# ALtiumSTM32_schematic.net
KiCad netlist of a schematic drawn in Altium Designer
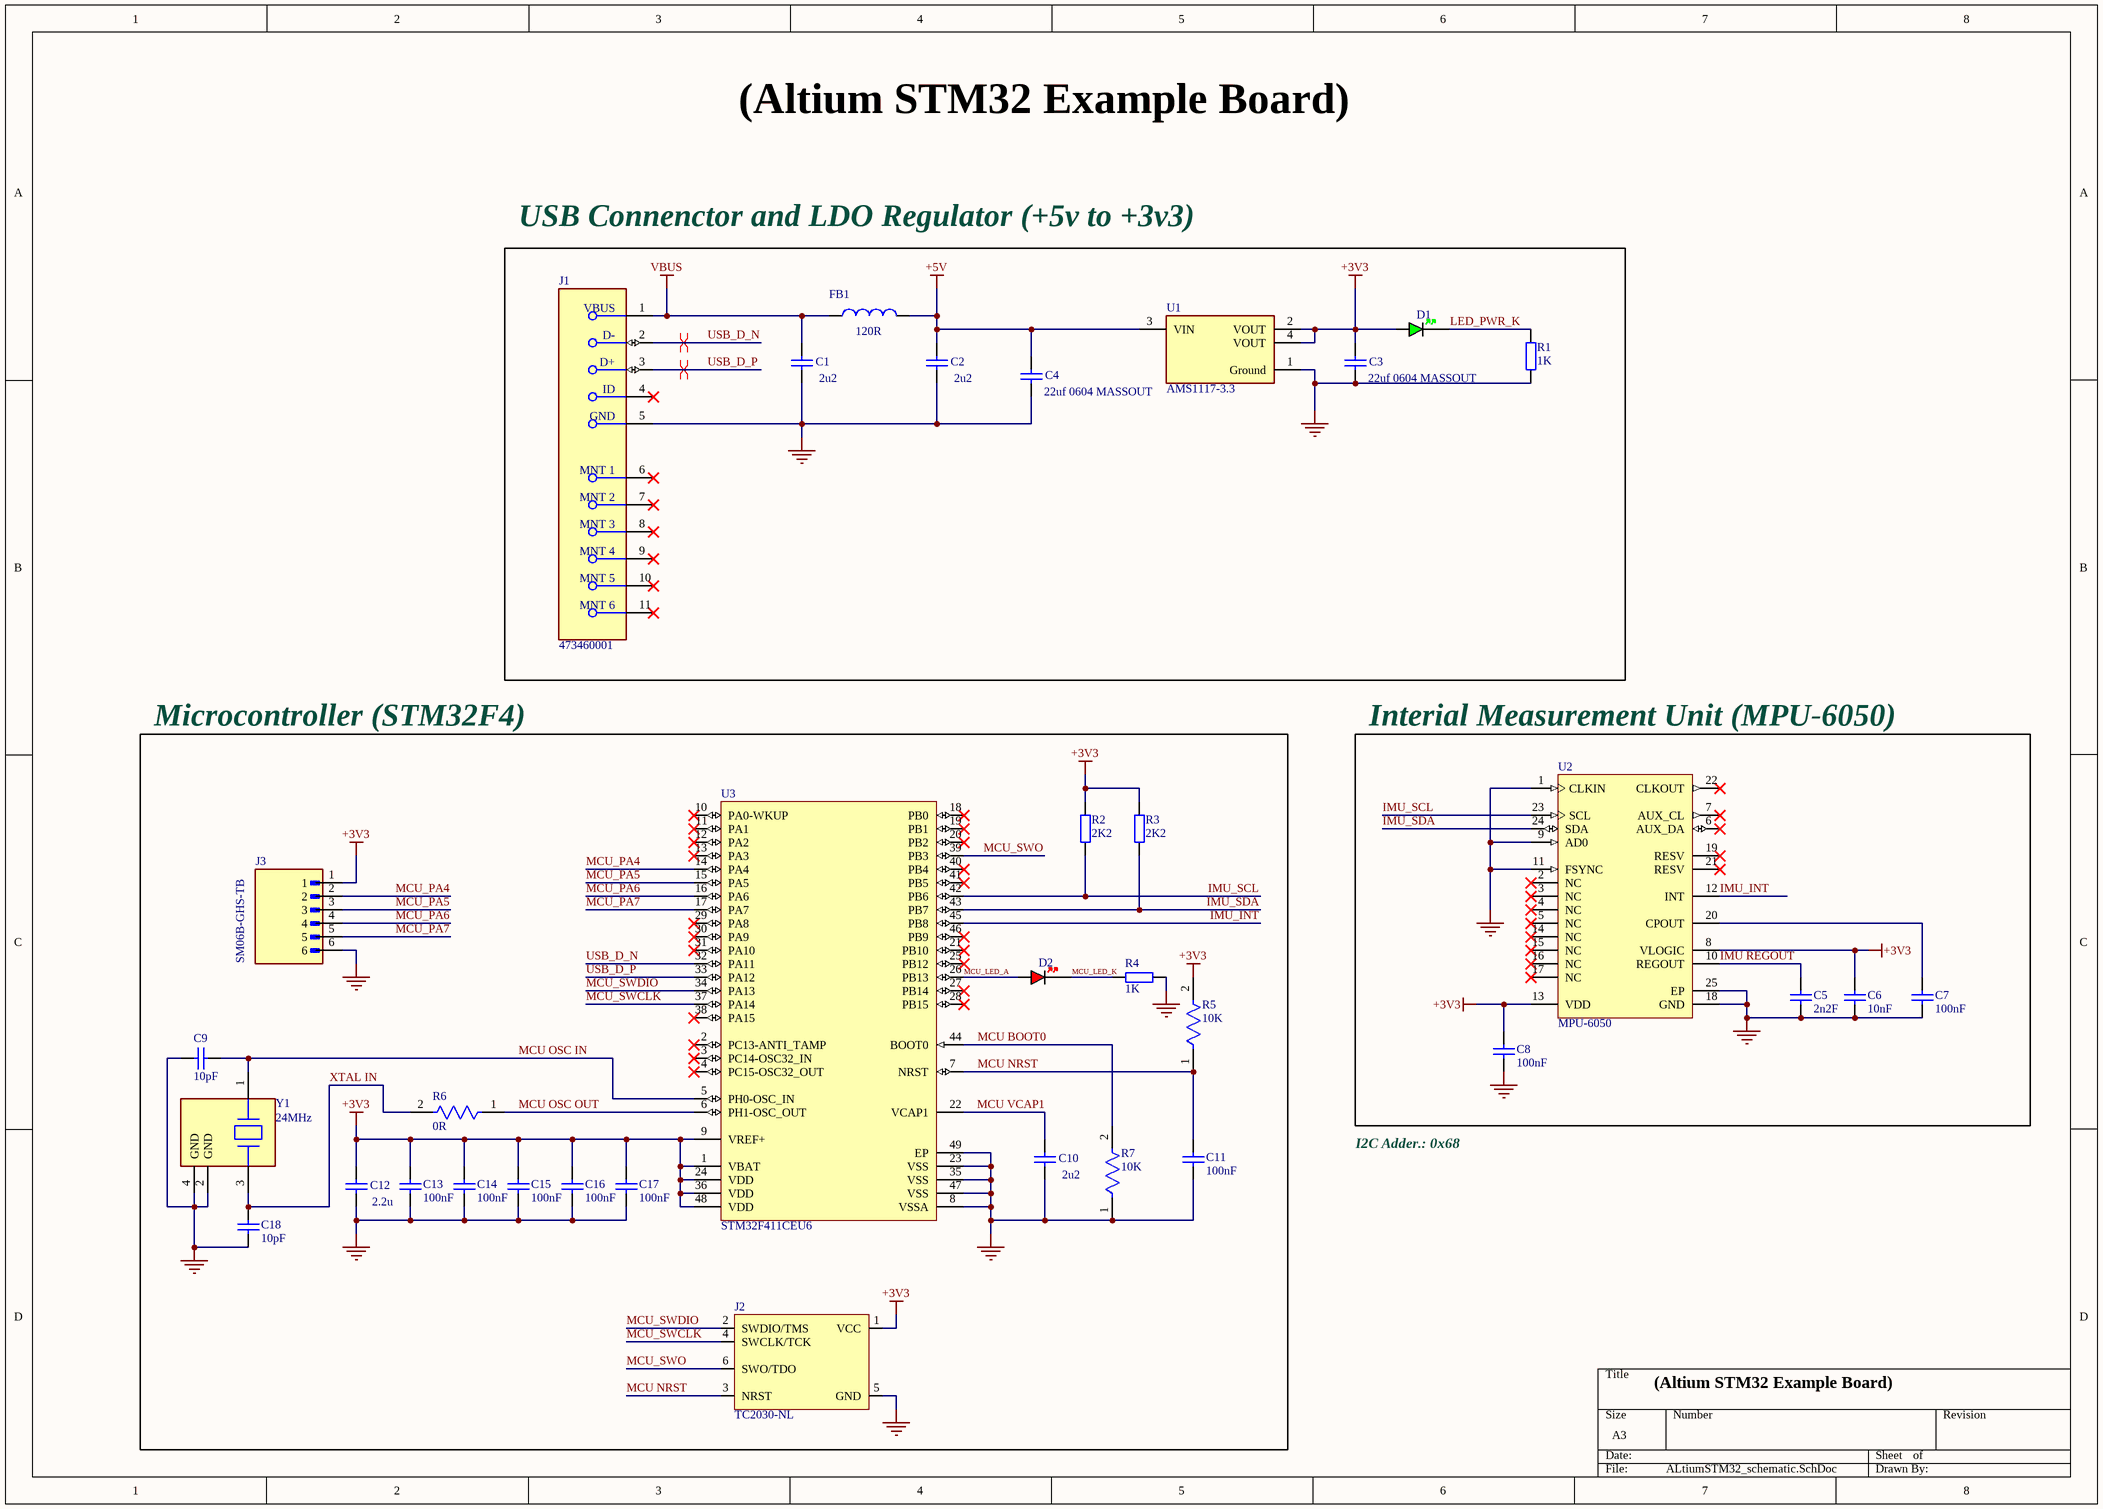
[diagram p0: ALtiumSTM32_schematic.SchDoc]

(export (version "E")
  (design (tool "Eeschema 10.0.6"))
  (components
    (comp (ref "C1")
      (value "2u2")
      (footprint "WCAP-CSGP_0603_L1.6W0.8H0.8_Reflow")
      (description "WCAP-CSGP 0603 (1608Metric) Ceramic Capacitor 0.063Lx0.031W 1.60mmx0.80mm X7R ±10% 220pF")
      (fields (field (name "TOLERANCE") "10%"))
      (libsource (lib "Altium Content Vault") (part "Capacitor_Non-Polarized"))
    )
    (comp (ref "C2")
      (value "2u2")
      (footprint "WCAP-CSGP_0603_L1.6W0.8H0.8_Reflow")
      (description "WCAP-CSGP 0603 (1608Metric) Ceramic Capacitor 0.063Lx0.031W 1.60mmx0.80mm X7R ±10% 220pF")
      (fields (field (name "TOLERANCE") "10%"))
      (libsource (lib "Altium Content Vault") (part "Capacitor_Non-Polarized"))
    )
    (comp (ref "C3")
      (value "22uf 0604 MASSOUT")
      (footprint "WCAP-CSGP_0603_L1.6W0.8H0.8_Reflow")
      (description "WCAP-CSGP 0603 (1608Metric) Ceramic Capacitor 0.063Lx0.031W 1.60mmx0.80mm X7R ±10% 220pF")
      (fields (field (name "TOLERANCE") "10%"))
      (libsource (lib "Altium Content Vault") (part "Capacitor_Non-Polarized"))
    )
    (comp (ref "C4")
      (value "22uf 0604 MASSOUT")
      (footprint "WCAP-CSGP_0603_L1.6W0.8H0.8_Reflow")
      (description "WCAP-CSGP 0603 (1608Metric) Ceramic Capacitor 0.063Lx0.031W 1.60mmx0.80mm X7R ±10% 220pF")
      (fields (field (name "TOLERANCE") "10%"))
      (libsource (lib "Altium Content Vault") (part "Capacitor_Non-Polarized"))
    )
    (comp (ref "C5")
      (value "2n2F")
      (footprint "CAPC1005X56X25LL10T15")
      (fields
        (field (name "PART NUMBER") "0402YD223KAT2A")
        (field (name "MANUFACTURER") "AVX Interconnect / Elco")
      )
      (libsource (lib "Altium Content Vault") (part "CAP"))
    )
    (comp (ref "C6")
      (value "10nF")
      (footprint "CAPC1005X56X25LL10T15")
      (fields
        (field (name "PART NUMBER") "0402YD223KAT2A")
        (field (name "MANUFACTURER") "AVX Interconnect / Elco")
      )
      (libsource (lib "Altium Content Vault") (part "CAP"))
    )
    (comp (ref "C7")
      (value "100nF")
      (footprint "CAPC1005X56X25LL10T15")
      (fields
        (field (name "PART NUMBER") "0402YD223KAT2A")
        (field (name "MANUFACTURER") "AVX Interconnect / Elco")
      )
      (libsource (lib "Altium Content Vault") (part "CAP"))
    )
    (comp (ref "C8")
      (value "100nF")
      (footprint "CAPC1005X56X25LL10T15")
      (fields
        (field (name "PART NUMBER") "0402YD223KAT2A")
        (field (name "MANUFACTURER") "AVX Interconnect / Elco")
      )
      (libsource (lib "Altium Content Vault") (part "CAP"))
    )
    (comp (ref "C9")
      (value "10pF")
      (footprint "CAPC1005X56X25LL10T15")
      (fields
        (field (name "PART NUMBER") "0402YD223KAT2A")
        (field (name "MANUFACTURER") "AVX Interconnect / Elco")
      )
      (libsource (lib "Altium Content Vault") (part "CAP"))
    )
    (comp (ref "C10")
      (value "2u2")
      (footprint "WCAP-CSGP_0603_L1.6W0.8H0.8_Reflow")
      (description "WCAP-CSGP 0603 (1608Metric) Ceramic Capacitor 0.063Lx0.031W 1.60mmx0.80mm X7R ±10% 220pF")
      (fields (field (name "TOLERANCE") "10%"))
      (libsource (lib "Altium Content Vault") (part "Capacitor_Non-Polarized"))
    )
    (comp (ref "C11")
      (value "100nF")
      (footprint "CAPC1005X56X25LL10T15")
      (fields
        (field (name "PART NUMBER") "0402YD223KAT2A")
        (field (name "MANUFACTURER") "AVX Interconnect / Elco")
      )
      (libsource (lib "Altium Content Vault") (part "CAP"))
    )
    (comp (ref "C12")
      (value "2.2u")
      (footprint "WCAP-CSGP_0603_L1.6W0.8H0.8_Reflow")
      (description "WCAP-CSGP 0603 (1608Metric) Ceramic Capacitor 0.063Lx0.031W 1.60mmx0.80mm X7R ±10% 220pF")
      (fields (field (name "TOLERANCE") "10%"))
      (libsource (lib "Altium Content Vault") (part "Capacitor_Non-Polarized"))
    )
    (comp (ref "C13")
      (value "100nF")
      (footprint "CAPC1005X56X25LL10T15")
      (fields
        (field (name "PART NUMBER") "0402YD223KAT2A")
        (field (name "MANUFACTURER") "AVX Interconnect / Elco")
      )
      (libsource (lib "Altium Content Vault") (part "CAP"))
    )
    (comp (ref "C14")
      (value "100nF")
      (footprint "CAPC1005X56X25LL10T15")
      (fields
        (field (name "PART NUMBER") "0402YD223KAT2A")
        (field (name "MANUFACTURER") "AVX Interconnect / Elco")
      )
      (libsource (lib "Altium Content Vault") (part "CAP"))
    )
    (comp (ref "C15")
      (value "100nF")
      (footprint "CAPC1005X56X25LL10T15")
      (fields
        (field (name "PART NUMBER") "0402YD223KAT2A")
        (field (name "MANUFACTURER") "AVX Interconnect / Elco")
      )
      (libsource (lib "Altium Content Vault") (part "CAP"))
    )
    (comp (ref "C16")
      (value "100nF")
      (footprint "CAPC1005X56X25LL10T15")
      (fields
        (field (name "PART NUMBER") "0402YD223KAT2A")
        (field (name "MANUFACTURER") "AVX Interconnect / Elco")
      )
      (libsource (lib "Altium Content Vault") (part "CAP"))
    )
    (comp (ref "C17")
      (value "100nF")
      (footprint "CAPC1005X56X25LL10T15")
      (fields
        (field (name "PART NUMBER") "0402YD223KAT2A")
        (field (name "MANUFACTURER") "AVX Interconnect / Elco")
      )
      (libsource (lib "Altium Content Vault") (part "CAP"))
    )
    (comp (ref "C18")
      (value "10pF")
      (footprint "CAPC1005X56X25LL10T15")
      (fields
        (field (name "PART NUMBER") "0402YD223KAT2A")
        (field (name "MANUFACTURER") "AVX Interconnect / Elco")
      )
      (libsource (lib "Altium Content Vault") (part "CAP"))
    )
    (comp (ref "D1")
      (value "GREEN")
      (footprint "LED_0402_GREEN")
      (description "LED 0402 GREEN SMD")
      (libsource (lib "*") (part "LED_0402_GREEN"))
    )
    (comp (ref "D2")
      (value "RED")
      (footprint "LED_0402_RED")
      (description "LED 0402 RED SMD")
      (libsource (lib "*") (part "LED_0402_RED"))
    )
    (comp (ref "FB1")
      (value "120R")
      (footprint "WE-CBF HF_0603_HC")
      (description "Ferrite Bead (emi Suppression), 1.6X0.8X0.8MM (0603), 600O Impedance At 100 Mhz")
      (fields (field (name "TOLERANCE") "25%"))
      (libsource (lib "Altium Content Vault") (part "Ferrite"))
    )
    (comp (ref "J1")
      (value "473460001")
      (footprint "FP-473460001-MFG")
      (description "CONN RCPT USB2.0 MICRO B SMD R/A")
      (fields
        (field (name "OCTOPART") "https://octopart.com/47346-0001-molex-7164928")
        (field (name "MANUFACTURER") "Molex")
      )
      (libsource (lib "Altium Content Vault") (part "53ae1f1d9b557310b43ca686e5bb76a"))
    )
    (comp (ref "J2")
      (value "TC2030-NL")
      (footprint "TC2030-NL-FP")
      (description "Tag-Connect No-Solder SWD Debug Connector (No Legs) DO NOT PLACE")
      (fields
        (field (name "MANUFACTURER") "Tag-Connect")
        (field (name "MANUFACTURER PART NUMBER") "TC2030-NL-FP")
      )
      (libsource (lib "*") (part "TC2030-NL"))
    )
    (comp (ref "J3")
      (value "SM06B-GHS-TB")
      (footprint "JST_SM06B-GHS-TB")
      (description "Connector Header Surface Mount, Right Angle 6 position 0.049 (1.25mm)")
      (fields (field (name "MF") "JST Sales"))
      (libsource (lib "omar Darwesh") (part "SM06B-GHS-TB"))
    )
    (comp (ref "R1")
      (value "1K")
      (footprint "RES_0402")
      (description "Resistor SMD 0402")
      (libsource (lib "*") (part "RES_0402"))
    )
    (comp (ref "R2")
      (value "2K2")
      (footprint "RES_0402")
      (description "Resistor SMD 0402")
      (libsource (lib "*") (part "RES_0402"))
    )
    (comp (ref "R3")
      (value "2K2")
      (footprint "RES_0402")
      (description "Resistor SMD 0402")
      (libsource (lib "*") (part "RES_0402"))
    )
    (comp (ref "R4")
      (value "1K")
      (footprint "RES_0402")
      (description "Resistor SMD 0402")
      (libsource (lib "*") (part "RES_0402"))
    )
    (comp (ref "R5")
      (value "10K")
      (footprint "FP-AC0402-MFG")
      (description "RES 11.3kΩ ±0.5% 0.063W 0402")
      (libsource (lib "Altium Content Vault") (part "1029c3af85768c4190bb7ad29bc67b5"))
    )
    (comp (ref "R6")
      (value "0R")
      (footprint "FP-AC0402-MFG")
      (description "RES 11.3kΩ ±0.5% 0.063W 0402")
      (libsource (lib "Altium Content Vault") (part "1029c3af85768c4190bb7ad29bc67b5"))
    )
    (comp (ref "R7")
      (value "10K")
      (footprint "FP-AC0402-MFG")
      (description "RES 11.3kΩ ±0.5% 0.063W 0402")
      (libsource (lib "Altium Content Vault") (part "1029c3af85768c4190bb7ad29bc67b5"))
    )
    (comp (ref "U1")
      (value "AMS1117-3.3")
      (footprint "FP-AMS1117-IPC_C")
      (description "LDO Voltage Regulators 1A, 3.3V")
      (fields
        (field (name "OCTOPART") "https://octopart.com/ams1117-3.3-advanced+monolithic+systems-25899300")
        (field (name "MANUFACTURER") "Advanced Monolithic Systems")
      )
      (libsource (lib "Altium Content Vault") (part "8bdbb5f8e77002000e30dd2845d0354"))
    )
    (comp (ref "U2")
      (value "MPU-6050")
      (footprint "IS-QFN-24_V")
      (fields (field (name "MANUFACTURER") "InvenSense"))
      (libsource (lib "Altium Content Vault") (part "IS-MPU-6050-QFN-24"))
    )
    (comp (ref "U3")
      (value "STM32F411CEU6")
      (footprint "STM-UFQFPN48_L")
      (libsource (lib "Altium Content Vault") (part "MC-ARM-STM32F411-UFQFPN48"))
    )
    (comp (ref "Y1")
      (value "24MHz")
      (footprint "FP-ABM10AIG-MFG")
      (description "Crystal 24MHz ±30ppm 10pF SMD-4 2.5mm x 2mm Automotive")
      (libsource (lib "Altium Content Vault") (part "40c3c19da1ce8e2d75e34138d1085e7"))
    )
  )
  (nets
    (net (code "1") (name "+3V3") (class "Default")
      (node (ref "C12") (pin "1") (pinfunction "1_1") (pintype "passive"))
      (node (ref "C13") (pin "2") (pinfunction "2_2") (pintype "passive"))
      (node (ref "C14") (pin "2") (pinfunction "2_2") (pintype "passive"))
      (node (ref "C15") (pin "2") (pinfunction "2_2") (pintype "passive"))
      (node (ref "C16") (pin "2") (pinfunction "2_2") (pintype "passive"))
      (node (ref "C17") (pin "2") (pinfunction "2_2") (pintype "passive"))
      (node (ref "C3") (pin "1") (pinfunction "1_1") (pintype "passive"))
      (node (ref "C6") (pin "2") (pinfunction "2_2") (pintype "passive"))
      (node (ref "C8") (pin "2") (pinfunction "2_2") (pintype "passive"))
      (node (ref "D1") (pin "A") (pinfunction "A_A") (pintype "passive"))
      (node (ref "J2") (pin "1") (pinfunction "VCC_1") (pintype "passive"))
      (node (ref "J3") (pin "1") (pinfunction "1_1") (pintype "passive"))
      (node (ref "R2") (pin "2") (pinfunction "2_2") (pintype "passive"))
      (node (ref "R3") (pin "2") (pinfunction "2_2") (pintype "passive"))
      (node (ref "R5") (pin "2") (pinfunction "2_2") (pintype "passive"))
      (node (ref "U1") (pin "2") (pinfunction "VOUT_2") (pintype "passive"))
      (node (ref "U1") (pin "4") (pinfunction "VOUT_4") (pintype "passive"))
      (node (ref "U2") (pin "13") (pinfunction "VDD_13") (pintype "power_in"))
      (node (ref "U2") (pin "8") (pinfunction "VLOGIC_8") (pintype "power_in"))
      (node (ref "U3") (pin "1") (pinfunction "VBAT_1") (pintype "power_in"))
      (node (ref "U3") (pin "24") (pinfunction "VDD_24") (pintype "power_in"))
      (node (ref "U3") (pin "36") (pinfunction "VDD_36") (pintype "power_in"))
      (node (ref "U3") (pin "48") (pinfunction "VDD_48") (pintype "power_in"))
      (node (ref "U3") (pin "9") (pinfunction "VREF+_9") (pintype "power_in"))
    )
    (net (code "2") (name "+5V") (class "Default")
      (node (ref "C2") (pin "1") (pinfunction "1_1") (pintype "passive"))
      (node (ref "C4") (pin "1") (pinfunction "1_1") (pintype "passive"))
      (node (ref "FB1") (pin "2") (pinfunction "2_2") (pintype "passive"))
      (node (ref "U1") (pin "3") (pinfunction "VIN_3") (pintype "power_in"))
    )
    (net (code "3") (name "/IMU REGOUT") (class "Default")
      (node (ref "C5") (pin "2") (pinfunction "2_2") (pintype "passive"))
      (node (ref "U2") (pin "10") (pinfunction "REGOUT_10") (pintype "passive"))
    )
    (net (code "4") (name "/IMU_INT") (class "Default")
      (node (ref "U2") (pin "12") (pinfunction "INT_12") (pintype "open_collector"))
      (node (ref "U3") (pin "45") (pinfunction "PB8_45") (pintype "bidirectional"))
    )
    (net (code "5") (name "/IMU_SCL") (class "Default")
      (node (ref "R2") (pin "1") (pinfunction "1_1") (pintype "passive"))
      (node (ref "U2") (pin "23") (pinfunction "SCL_23") (pintype "input"))
      (node (ref "U3") (pin "42") (pinfunction "PB6_42") (pintype "bidirectional"))
    )
    (net (code "6") (name "/IMU_SDA") (class "Default")
      (node (ref "R3") (pin "1") (pinfunction "1_1") (pintype "passive"))
      (node (ref "U2") (pin "24") (pinfunction "SDA_24") (pintype "bidirectional"))
      (node (ref "U3") (pin "43") (pinfunction "PB7_43") (pintype "bidirectional"))
    )
    (net (code "7") (name "/LED_PWR_K") (class "Default")
      (node (ref "D1") (pin "K") (pinfunction "K_K") (pintype "passive"))
      (node (ref "R1") (pin "2") (pinfunction "2_2") (pintype "passive"))
    )
    (net (code "8") (name "/MCU BOOT0") (class "Default")
      (node (ref "R7") (pin "2") (pinfunction "2_2") (pintype "passive"))
      (node (ref "U3") (pin "44") (pinfunction "BOOT0_44") (pintype "input"))
    )
    (net (code "9") (name "/MCU NRST") (class "Default")
      (node (ref "C11") (pin "2") (pinfunction "2_2") (pintype "passive"))
      (node (ref "J2") (pin "3") (pinfunction "NRST_3") (pintype "passive"))
      (node (ref "R5") (pin "1") (pinfunction "1_1") (pintype "passive"))
      (node (ref "U3") (pin "7") (pinfunction "NRST_7") (pintype "bidirectional"))
    )
    (net (code "10") (name "/MCU OSC IN") (class "Default")
      (node (ref "C9") (pin "1") (pinfunction "1_1") (pintype "passive"))
      (node (ref "U3") (pin "5") (pinfunction "PH0-OSC_IN_5") (pintype "bidirectional"))
      (node (ref "Y1") (pin "1") (pinfunction "1_Crystal_1") (pintype "passive"))
    )
    (net (code "11") (name "/MCU OSC OUT") (class "Default")
      (node (ref "R6") (pin "1") (pinfunction "1_1") (pintype "passive"))
      (node (ref "U3") (pin "6") (pinfunction "PH1-OSC_OUT_6") (pintype "bidirectional"))
    )
    (net (code "12") (name "/MCU VCAP1") (class "Default")
      (node (ref "C10") (pin "1") (pinfunction "1_1") (pintype "passive"))
      (node (ref "U3") (pin "22") (pinfunction "VCAP1_22") (pintype "passive"))
    )
    (net (code "13") (name "/MCU_LED_A") (class "Default")
      (node (ref "D2") (pin "A") (pinfunction "A_A") (pintype "passive"))
      (node (ref "U3") (pin "26") (pinfunction "PB13_26") (pintype "bidirectional"))
    )
    (net (code "14") (name "/MCU_LED_K") (class "Default")
      (node (ref "D2") (pin "K") (pinfunction "K_K") (pintype "passive"))
      (node (ref "R4") (pin "2") (pinfunction "2_2") (pintype "passive"))
    )
    (net (code "15") (name "/MCU_PA4") (class "Default")
      (node (ref "J3") (pin "2") (pinfunction "2_2") (pintype "passive"))
      (node (ref "U3") (pin "14") (pinfunction "PA4_14") (pintype "bidirectional"))
    )
    (net (code "16") (name "/MCU_PA5") (class "Default")
      (node (ref "J3") (pin "3") (pinfunction "3_3") (pintype "passive"))
      (node (ref "U3") (pin "15") (pinfunction "PA5_15") (pintype "bidirectional"))
    )
    (net (code "17") (name "/MCU_PA6") (class "Default")
      (node (ref "J3") (pin "4") (pinfunction "4_4") (pintype "passive"))
      (node (ref "U3") (pin "16") (pinfunction "PA6_16") (pintype "bidirectional"))
    )
    (net (code "18") (name "/MCU_PA7") (class "Default")
      (node (ref "J3") (pin "5") (pinfunction "5_5") (pintype "passive"))
      (node (ref "U3") (pin "17") (pinfunction "PA7_17") (pintype "bidirectional"))
    )
    (net (code "19") (name "/MCU_SWCLK") (class "Default")
      (node (ref "J2") (pin "4") (pinfunction "SWCLK/TCK_4") (pintype "passive"))
      (node (ref "U3") (pin "37") (pinfunction "PA14_37") (pintype "bidirectional"))
    )
    (net (code "20") (name "/MCU_SWDIO") (class "Default")
      (node (ref "J2") (pin "2") (pinfunction "SWDIO/TMS_2") (pintype "passive"))
      (node (ref "U3") (pin "34") (pinfunction "PA13_34") (pintype "bidirectional"))
    )
    (net (code "21") (name "/MCU_SWO") (class "Default")
      (node (ref "J2") (pin "6") (pinfunction "SWO/TDO_6") (pintype "passive"))
      (node (ref "U3") (pin "39") (pinfunction "PB3_39") (pintype "bidirectional"))
    )
    (net (code "22") (name "/USB_D_N") (class "Default")
      (node (ref "J1") (pin "2") (pinfunction "D-_2") (pintype "bidirectional"))
      (node (ref "U3") (pin "32") (pinfunction "PA11_32") (pintype "bidirectional"))
    )
    (net (code "23") (name "/USB_D_P") (class "Default")
      (node (ref "J1") (pin "3") (pinfunction "D+_3") (pintype "bidirectional"))
      (node (ref "U3") (pin "33") (pinfunction "PA12_33") (pintype "bidirectional"))
    )
    (net (code "24") (name "/XTAL IN") (class "Default")
      (node (ref "C18") (pin "2") (pinfunction "2_2") (pintype "passive"))
      (node (ref "R6") (pin "2") (pinfunction "2_2") (pintype "passive"))
      (node (ref "Y1") (pin "3") (pinfunction "2_Crystal_3") (pintype "passive"))
    )
    (net (code "25") (name "GND") (class "Default")
      (node (ref "C1") (pin "2") (pinfunction "2_2") (pintype "passive"))
      (node (ref "C10") (pin "2") (pinfunction "2_2") (pintype "passive"))
      (node (ref "C11") (pin "1") (pinfunction "1_1") (pintype "passive"))
      (node (ref "C12") (pin "2") (pinfunction "2_2") (pintype "passive"))
      (node (ref "C13") (pin "1") (pinfunction "1_1") (pintype "passive"))
      (node (ref "C14") (pin "1") (pinfunction "1_1") (pintype "passive"))
      (node (ref "C15") (pin "1") (pinfunction "1_1") (pintype "passive"))
      (node (ref "C16") (pin "1") (pinfunction "1_1") (pintype "passive"))
      (node (ref "C17") (pin "1") (pinfunction "1_1") (pintype "passive"))
      (node (ref "C18") (pin "1") (pinfunction "1_1") (pintype "passive"))
      (node (ref "C2") (pin "2") (pinfunction "2_2") (pintype "passive"))
      (node (ref "C3") (pin "2") (pinfunction "2_2") (pintype "passive"))
      (node (ref "C4") (pin "2") (pinfunction "2_2") (pintype "passive"))
      (node (ref "C5") (pin "1") (pinfunction "1_1") (pintype "passive"))
      (node (ref "C6") (pin "1") (pinfunction "1_1") (pintype "passive"))
      (node (ref "C7") (pin "1") (pinfunction "1_1") (pintype "passive"))
      (node (ref "C8") (pin "1") (pinfunction "1_1") (pintype "passive"))
      (node (ref "C9") (pin "2") (pinfunction "2_2") (pintype "passive"))
      (node (ref "J1") (pin "5") (pinfunction "GND_5") (pintype "power_in"))
      (node (ref "J2") (pin "5") (pinfunction "GND_5") (pintype "passive"))
      (node (ref "J3") (pin "6") (pinfunction "6_6") (pintype "passive"))
      (node (ref "R1") (pin "1") (pinfunction "1_1") (pintype "passive"))
      (node (ref "R4") (pin "1") (pinfunction "1_1") (pintype "passive"))
      (node (ref "R7") (pin "1") (pinfunction "1_1") (pintype "passive"))
      (node (ref "U1") (pin "1") (pinfunction "Ground_1") (pintype "power_in"))
      (node (ref "U2") (pin "1") (pinfunction "CLKIN_1") (pintype "input"))
      (node (ref "U2") (pin "11") (pinfunction "FSYNC_11") (pintype "input"))
      (node (ref "U2") (pin "18") (pinfunction "GND_18") (pintype "power_in"))
      (node (ref "U2") (pin "25") (pinfunction "EP_25") (pintype "power_in"))
      (node (ref "U2") (pin "9") (pinfunction "AD0_9") (pintype "input"))
      (node (ref "U3") (pin "23") (pinfunction "VSS_23") (pintype "power_in"))
      (node (ref "U3") (pin "35") (pinfunction "VSS_35") (pintype "power_in"))
      (node (ref "U3") (pin "47") (pinfunction "VSS_47") (pintype "power_in"))
      (node (ref "U3") (pin "49") (pinfunction "EP_49") (pintype "power_in"))
      (node (ref "U3") (pin "8") (pinfunction "VSSA_8") (pintype "power_in"))
      (node (ref "Y1") (pin "2") (pinfunction "GND_2") (pintype "power_in"))
      (node (ref "Y1") (pin "4") (pinfunction "GND_4") (pintype "power_in"))
    )
    (net (code "26") (name "Net-(U2-CPOUT)") (class "Default")
      (node (ref "C7") (pin "2") (pinfunction "2_2") (pintype "passive"))
      (node (ref "U2") (pin "20") (pinfunction "CPOUT_20") (pintype "passive"))
    )
    (net (code "27") (name "VBUS") (class "Default")
      (node (ref "C1") (pin "1") (pinfunction "1_1") (pintype "passive"))
      (node (ref "FB1") (pin "1") (pinfunction "1_1") (pintype "passive"))
      (node (ref "J1") (pin "1") (pinfunction "VBUS_1") (pintype "power_in"))
    )
    (net (code "28") (name "unconnected-(J1-ID-Pad4)") (class "Default")
      (node (ref "J1") (pin "4") (pinfunction "ID_4") (pintype "passive+no_connect"))
    )
    (net (code "29") (name "unconnected-(J1-MNT_1-Pad6)") (class "Default")
      (node (ref "J1") (pin "6") (pinfunction "MNT_1_6") (pintype "passive+no_connect"))
    )
    (net (code "30") (name "unconnected-(J1-MNT_2-Pad7)") (class "Default")
      (node (ref "J1") (pin "7") (pinfunction "MNT_2_7") (pintype "passive+no_connect"))
    )
    (net (code "31") (name "unconnected-(J1-MNT_3-Pad8)") (class "Default")
      (node (ref "J1") (pin "8") (pinfunction "MNT_3_8") (pintype "passive+no_connect"))
    )
    (net (code "32") (name "unconnected-(J1-MNT_4-Pad9)") (class "Default")
      (node (ref "J1") (pin "9") (pinfunction "MNT_4_9") (pintype "passive+no_connect"))
    )
    (net (code "33") (name "unconnected-(J1-MNT_5-Pad10)") (class "Default")
      (node (ref "J1") (pin "10") (pinfunction "MNT_5_10") (pintype "passive+no_connect"))
    )
    (net (code "34") (name "unconnected-(J1-MNT_6-Pad11)") (class "Default")
      (node (ref "J1") (pin "11") (pinfunction "MNT_6_11") (pintype "passive+no_connect"))
    )
    (net (code "35") (name "unconnected-(U2-AUX_CL-Pad7)") (class "Default")
      (node (ref "U2") (pin "7") (pinfunction "AUX_CL_7") (pintype "output+no_connect"))
    )
    (net (code "36") (name "unconnected-(U2-AUX_DA-Pad6)") (class "Default")
      (node (ref "U2") (pin "6") (pinfunction "AUX_DA_6") (pintype "bidirectional+no_connect"))
    )
    (net (code "37") (name "unconnected-(U2-CLKOUT-Pad22)") (class "Default")
      (node (ref "U2") (pin "22") (pinfunction "CLKOUT_22") (pintype "output+no_connect"))
    )
    (net (code "38") (name "unconnected-(U2-NC-Pad2)") (class "Default")
      (node (ref "U2") (pin "2") (pinfunction "NC_2") (pintype "passive+no_connect"))
    )
    (net (code "39") (name "unconnected-(U2-NC-Pad3)") (class "Default")
      (node (ref "U2") (pin "3") (pinfunction "NC_3") (pintype "passive+no_connect"))
    )
    (net (code "40") (name "unconnected-(U2-NC-Pad4)") (class "Default")
      (node (ref "U2") (pin "4") (pinfunction "NC_4") (pintype "passive+no_connect"))
    )
    (net (code "41") (name "unconnected-(U2-NC-Pad5)") (class "Default")
      (node (ref "U2") (pin "5") (pinfunction "NC_5") (pintype "passive+no_connect"))
    )
    (net (code "42") (name "unconnected-(U2-NC-Pad14)") (class "Default")
      (node (ref "U2") (pin "14") (pinfunction "NC_14") (pintype "passive+no_connect"))
    )
    (net (code "43") (name "unconnected-(U2-NC-Pad15)") (class "Default")
      (node (ref "U2") (pin "15") (pinfunction "NC_15") (pintype "passive+no_connect"))
    )
    (net (code "44") (name "unconnected-(U2-NC-Pad16)") (class "Default")
      (node (ref "U2") (pin "16") (pinfunction "NC_16") (pintype "passive+no_connect"))
    )
    (net (code "45") (name "unconnected-(U2-NC-Pad17)") (class "Default")
      (node (ref "U2") (pin "17") (pinfunction "NC_17") (pintype "passive+no_connect"))
    )
    (net (code "46") (name "unconnected-(U2-RESV-Pad19)") (class "Default")
      (node (ref "U2") (pin "19") (pinfunction "RESV_19") (pintype "passive+no_connect"))
    )
    (net (code "47") (name "unconnected-(U2-RESV-Pad21)") (class "Default")
      (node (ref "U2") (pin "21") (pinfunction "RESV_21") (pintype "passive+no_connect"))
    )
    (net (code "48") (name "unconnected-(U3-PA0-WKUP-Pad10)") (class "Default")
      (node (ref "U3") (pin "10") (pinfunction "PA0-WKUP_10") (pintype "bidirectional+no_connect"))
    )
    (net (code "49") (name "unconnected-(U3-PA1-Pad11)") (class "Default")
      (node (ref "U3") (pin "11") (pinfunction "PA1_11") (pintype "bidirectional+no_connect"))
    )
    (net (code "50") (name "unconnected-(U3-PA2-Pad12)") (class "Default")
      (node (ref "U3") (pin "12") (pinfunction "PA2_12") (pintype "bidirectional+no_connect"))
    )
    (net (code "51") (name "unconnected-(U3-PA3-Pad13)") (class "Default")
      (node (ref "U3") (pin "13") (pinfunction "PA3_13") (pintype "bidirectional+no_connect"))
    )
    (net (code "52") (name "unconnected-(U3-PA8-Pad29)") (class "Default")
      (node (ref "U3") (pin "29") (pinfunction "PA8_29") (pintype "bidirectional+no_connect"))
    )
    (net (code "53") (name "unconnected-(U3-PA9-Pad30)") (class "Default")
      (node (ref "U3") (pin "30") (pinfunction "PA9_30") (pintype "bidirectional+no_connect"))
    )
    (net (code "54") (name "unconnected-(U3-PA10-Pad31)") (class "Default")
      (node (ref "U3") (pin "31") (pinfunction "PA10_31") (pintype "bidirectional+no_connect"))
    )
    (net (code "55") (name "unconnected-(U3-PA15-Pad38)") (class "Default")
      (node (ref "U3") (pin "38") (pinfunction "PA15_38") (pintype "bidirectional+no_connect"))
    )
    (net (code "56") (name "unconnected-(U3-PB0-Pad18)") (class "Default")
      (node (ref "U3") (pin "18") (pinfunction "PB0_18") (pintype "bidirectional+no_connect"))
    )
    (net (code "57") (name "unconnected-(U3-PB1-Pad19)") (class "Default")
      (node (ref "U3") (pin "19") (pinfunction "PB1_19") (pintype "bidirectional+no_connect"))
    )
    (net (code "58") (name "unconnected-(U3-PB2-Pad20)") (class "Default")
      (node (ref "U3") (pin "20") (pinfunction "PB2_20") (pintype "bidirectional+no_connect"))
    )
    (net (code "59") (name "unconnected-(U3-PB4-Pad40)") (class "Default")
      (node (ref "U3") (pin "40") (pinfunction "PB4_40") (pintype "bidirectional+no_connect"))
    )
    (net (code "60") (name "unconnected-(U3-PB5-Pad41)") (class "Default")
      (node (ref "U3") (pin "41") (pinfunction "PB5_41") (pintype "bidirectional+no_connect"))
    )
    (net (code "61") (name "unconnected-(U3-PB9-Pad46)") (class "Default")
      (node (ref "U3") (pin "46") (pinfunction "PB9_46") (pintype "bidirectional+no_connect"))
    )
    (net (code "62") (name "unconnected-(U3-PB10-Pad21)") (class "Default")
      (node (ref "U3") (pin "21") (pinfunction "PB10_21") (pintype "bidirectional+no_connect"))
    )
    (net (code "63") (name "unconnected-(U3-PB12-Pad25)") (class "Default")
      (node (ref "U3") (pin "25") (pinfunction "PB12_25") (pintype "bidirectional+no_connect"))
    )
    (net (code "64") (name "unconnected-(U3-PB14-Pad27)") (class "Default")
      (node (ref "U3") (pin "27") (pinfunction "PB14_27") (pintype "bidirectional+no_connect"))
    )
    (net (code "65") (name "unconnected-(U3-PB15-Pad28)") (class "Default")
      (node (ref "U3") (pin "28") (pinfunction "PB15_28") (pintype "bidirectional+no_connect"))
    )
    (net (code "66") (name "unconnected-(U3-PC13-ANTI_TAMP-Pad2)") (class "Default")
      (node (ref "U3") (pin "2") (pinfunction "PC13-ANTI_TAMP_2") (pintype "bidirectional+no_connect"))
    )
    (net (code "67") (name "unconnected-(U3-PC14-OSC32_IN-Pad3)") (class "Default")
      (node (ref "U3") (pin "3") (pinfunction "PC14-OSC32_IN_3") (pintype "bidirectional+no_connect"))
    )
    (net (code "68") (name "unconnected-(U3-PC15-OSC32_OUT-Pad4)") (class "Default")
      (node (ref "U3") (pin "4") (pinfunction "PC15-OSC32_OUT_4") (pintype "bidirectional+no_connect"))
    )
  )
)
